# 1-Schematic_Raspberry_Pi2.net
KiCad netlist of a schematic drawn in EasyEDA
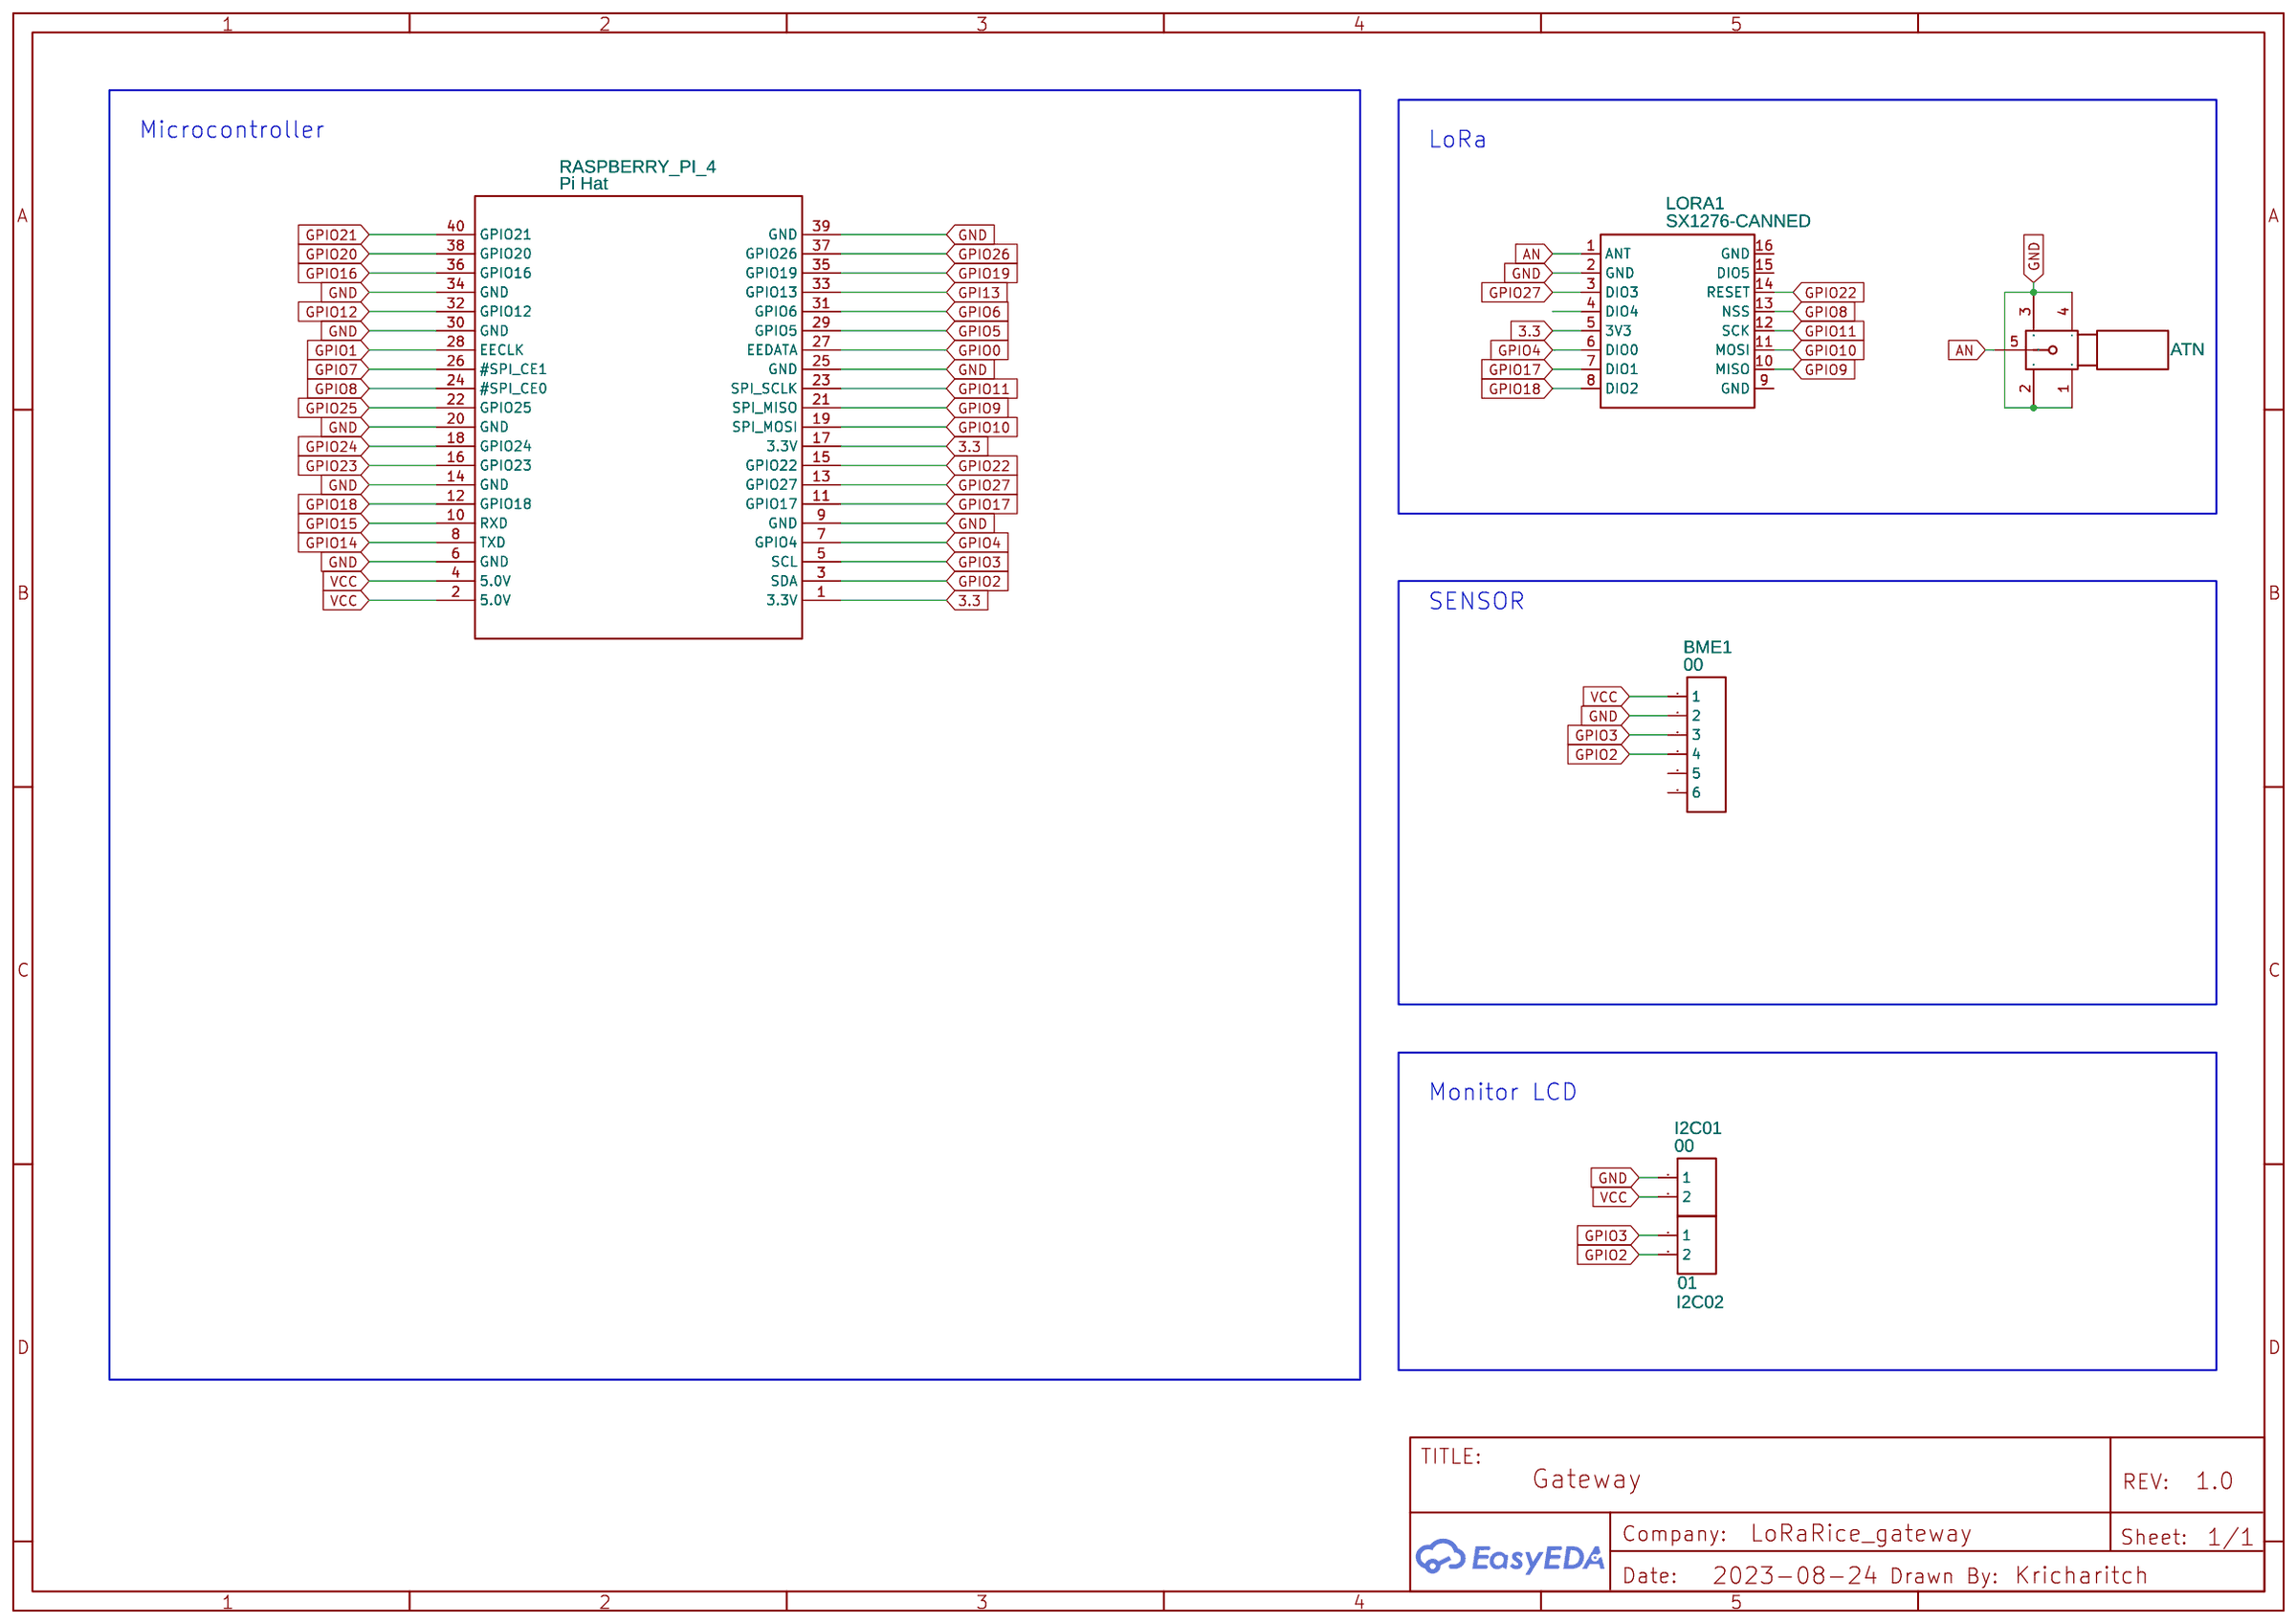
[diagram p0: schematic sheet]

(export (version "E")
  (design (tool "Eeschema 10.0.6"))
  (components
    (comp (ref "BME1") (value "00") (libsource (lib "") (part "HDR-F-2.54_1x6")))
    (comp (ref "I2C01") (value "00") (libsource (lib "") (part "CONN-TH_2P-P5.00")))
    (comp (ref "I2C02") (value "01") (libsource (lib "") (part "CONN-TH_2P-P5.00")))
    (comp (ref "LORA1")
      (value "SX1276-CANNED")
      (fields (field (name "Manufacturer Part") "LoRa1276-C1") (field (name "Manufacturer") "G-NiceRF"))
      (libsource (lib "") (part "SX1276-CANNED"))
    )
    (comp (ref "RASPBERRY_PI_4") (value "Pi Hat") (libsource (lib "") (part "Unknown_280_-75")))
    (comp (ref "RF1")
      (value "ATN")
      (fields
        (field (name "Manufacturer Part") "BWSMA-KE-P001")
        (field (name "Manufacturer") "BAT WIRELESS(蝙蝠无线)")
      )
      (libsource (lib "") (part "BWSMA-KE-P001"))
    )
  )
  (nets
    (net (code "1") (name "3.3") (class "Default")
      (node (ref "LORA1") (pin "5") (pinfunction "3V3_5") (pintype "unspecified"))
      (node (ref "RASPBERRY_PI_4") (pin "1") (pinfunction "3.3V_1") (pintype "unspecified"))
      (node (ref "RASPBERRY_PI_4") (pin "17") (pinfunction "3.3V_17") (pintype "unspecified"))
    )
    (net (code "2") (name "AN") (class "Default")
      (node (ref "LORA1") (pin "1") (pinfunction "ANT_1") (pintype "unspecified"))
      (node (ref "RF1") (pin "5") (pinfunction "5_5") (pintype "unspecified"))
    )
    (net (code "3") (name "GND") (class "Default")
      (node (ref "BME1") (pin "2") (pinfunction "2_2") (pintype "input"))
      (node (ref "I2C01") (pin "1") (pinfunction "1_1") (pintype "unspecified"))
      (node (ref "LORA1") (pin "2") (pinfunction "GND_2") (pintype "unspecified"))
      (node (ref "RASPBERRY_PI_4") (pin "14") (pinfunction "GND_14") (pintype "unspecified"))
      (node (ref "RASPBERRY_PI_4") (pin "20") (pinfunction "GND_20") (pintype "unspecified"))
      (node (ref "RASPBERRY_PI_4") (pin "25") (pinfunction "GND_25") (pintype "unspecified"))
      (node (ref "RASPBERRY_PI_4") (pin "30") (pinfunction "GND_30") (pintype "unspecified"))
      (node (ref "RASPBERRY_PI_4") (pin "34") (pinfunction "GND_34") (pintype "unspecified"))
      (node (ref "RASPBERRY_PI_4") (pin "39") (pinfunction "GND_39") (pintype "unspecified"))
      (node (ref "RASPBERRY_PI_4") (pin "6") (pinfunction "GND_6") (pintype "unspecified"))
      (node (ref "RASPBERRY_PI_4") (pin "9") (pinfunction "GND_9") (pintype "unspecified"))
      (node (ref "RF1") (pin "1") (pinfunction "1_1") (pintype "unspecified"))
      (node (ref "RF1") (pin "2") (pinfunction "2_2") (pintype "unspecified"))
      (node (ref "RF1") (pin "3") (pinfunction "3_3") (pintype "unspecified"))
      (node (ref "RF1") (pin "4") (pinfunction "4_4") (pintype "unspecified"))
    )
    (net (code "4") (name "GPI13") (class "Default")
      (node (ref "RASPBERRY_PI_4") (pin "33") (pinfunction "GPIO13_33") (pintype "unspecified"))
    )
    (net (code "5") (name "GPIO0") (class "Default")
      (node (ref "RASPBERRY_PI_4") (pin "27") (pinfunction "EEDATA_27") (pintype "unspecified"))
    )
    (net (code "6") (name "GPIO1") (class "Default")
      (node (ref "RASPBERRY_PI_4") (pin "28") (pinfunction "EECLK_28") (pintype "unspecified"))
    )
    (net (code "7") (name "GPIO2") (class "Default")
      (node (ref "BME1") (pin "4") (pinfunction "4_4") (pintype "input"))
      (node (ref "I2C02") (pin "2") (pinfunction "2_2") (pintype "unspecified"))
      (node (ref "RASPBERRY_PI_4") (pin "3") (pinfunction "SDA_3") (pintype "unspecified"))
    )
    (net (code "8") (name "GPIO3") (class "Default")
      (node (ref "BME1") (pin "3") (pinfunction "3_3") (pintype "input"))
      (node (ref "I2C02") (pin "1") (pinfunction "1_1") (pintype "unspecified"))
      (node (ref "RASPBERRY_PI_4") (pin "5") (pinfunction "SCL_5") (pintype "unspecified"))
    )
    (net (code "9") (name "GPIO4") (class "Default")
      (node (ref "LORA1") (pin "6") (pinfunction "DIO0_6") (pintype "unspecified"))
      (node (ref "RASPBERRY_PI_4") (pin "7") (pinfunction "GPIO4_7") (pintype "unspecified"))
    )
    (net (code "10") (name "GPIO5") (class "Default")
      (node (ref "RASPBERRY_PI_4") (pin "29") (pinfunction "GPIO5_29") (pintype "unspecified"))
    )
    (net (code "11") (name "GPIO6") (class "Default")
      (node (ref "RASPBERRY_PI_4") (pin "31") (pinfunction "GPIO6_31") (pintype "unspecified"))
    )
    (net (code "12") (name "GPIO7") (class "Default")
      (node (ref "RASPBERRY_PI_4") (pin "26") (pinfunction "#SPI_CE1_26") (pintype "unspecified"))
    )
    (net (code "13") (name "GPIO8") (class "Default")
      (node (ref "LORA1") (pin "13") (pinfunction "NSS_13") (pintype "unspecified"))
      (node (ref "RASPBERRY_PI_4") (pin "24") (pinfunction "#SPI_CE0_24") (pintype "unspecified"))
    )
    (net (code "14") (name "GPIO9") (class "Default")
      (node (ref "LORA1") (pin "10") (pinfunction "MISO_10") (pintype "unspecified"))
      (node (ref "RASPBERRY_PI_4") (pin "21") (pinfunction "SPI_MISO_21") (pintype "unspecified"))
    )
    (net (code "15") (name "GPIO10") (class "Default")
      (node (ref "LORA1") (pin "11") (pinfunction "MOSI_11") (pintype "unspecified"))
      (node (ref "RASPBERRY_PI_4") (pin "19") (pinfunction "SPI_MOSI_19") (pintype "unspecified"))
    )
    (net (code "16") (name "GPIO11") (class "Default")
      (node (ref "LORA1") (pin "12") (pinfunction "SCK_12") (pintype "unspecified"))
      (node (ref "RASPBERRY_PI_4") (pin "23") (pinfunction "SPI_SCLK_23") (pintype "unspecified"))
    )
    (net (code "17") (name "GPIO12") (class "Default")
      (node (ref "RASPBERRY_PI_4") (pin "32") (pinfunction "GPIO12_32") (pintype "unspecified"))
    )
    (net (code "18") (name "GPIO14") (class "Default")
      (node (ref "RASPBERRY_PI_4") (pin "8") (pinfunction "TXD_8") (pintype "output"))
    )
    (net (code "19") (name "GPIO15") (class "Default")
      (node (ref "RASPBERRY_PI_4") (pin "10") (pinfunction "RXD_10") (pintype "unspecified"))
    )
    (net (code "20") (name "GPIO16") (class "Default")
      (node (ref "RASPBERRY_PI_4") (pin "36") (pinfunction "GPIO16_36") (pintype "unspecified"))
    )
    (net (code "21") (name "GPIO17") (class "Default")
      (node (ref "LORA1") (pin "7") (pinfunction "DIO1_7") (pintype "unspecified"))
      (node (ref "RASPBERRY_PI_4") (pin "11") (pinfunction "GPIO17_11") (pintype "unspecified"))
    )
    (net (code "22") (name "GPIO18") (class "Default")
      (node (ref "LORA1") (pin "8") (pinfunction "DIO2_8") (pintype "unspecified"))
      (node (ref "RASPBERRY_PI_4") (pin "12") (pinfunction "GPIO18_12") (pintype "unspecified"))
    )
    (net (code "23") (name "GPIO19") (class "Default")
      (node (ref "RASPBERRY_PI_4") (pin "35") (pinfunction "GPIO19_35") (pintype "unspecified"))
    )
    (net (code "24") (name "GPIO20") (class "Default")
      (node (ref "RASPBERRY_PI_4") (pin "38") (pinfunction "GPIO20_38") (pintype "unspecified"))
    )
    (net (code "25") (name "GPIO21") (class "Default")
      (node (ref "RASPBERRY_PI_4") (pin "40") (pinfunction "GPIO21_40") (pintype "unspecified"))
    )
    (net (code "26") (name "GPIO22") (class "Default")
      (node (ref "LORA1") (pin "14") (pinfunction "RESET_14") (pintype "unspecified"))
      (node (ref "RASPBERRY_PI_4") (pin "15") (pinfunction "GPIO22_15") (pintype "unspecified"))
    )
    (net (code "27") (name "GPIO23") (class "Default")
      (node (ref "RASPBERRY_PI_4") (pin "16") (pinfunction "GPIO23_16") (pintype "unspecified"))
    )
    (net (code "28") (name "GPIO24") (class "Default")
      (node (ref "RASPBERRY_PI_4") (pin "18") (pinfunction "GPIO24_18") (pintype "unspecified"))
    )
    (net (code "29") (name "GPIO25") (class "Default")
      (node (ref "RASPBERRY_PI_4") (pin "22") (pinfunction "GPIO25_22") (pintype "unspecified"))
    )
    (net (code "30") (name "GPIO26") (class "Default")
      (node (ref "RASPBERRY_PI_4") (pin "37") (pinfunction "GPIO26_37") (pintype "unspecified"))
    )
    (net (code "31") (name "GPIO27") (class "Default")
      (node (ref "LORA1") (pin "3") (pinfunction "DIO3_3") (pintype "unspecified"))
      (node (ref "RASPBERRY_PI_4") (pin "13") (pinfunction "GPIO27_13") (pintype "unspecified"))
    )
    (net (code "32") (name "VCC") (class "Default")
      (node (ref "BME1") (pin "1") (pinfunction "1_1") (pintype "input"))
      (node (ref "I2C01") (pin "2") (pinfunction "2_2") (pintype "unspecified"))
      (node (ref "RASPBERRY_PI_4") (pin "2") (pinfunction "5.0V_2") (pintype "unspecified"))
      (node (ref "RASPBERRY_PI_4") (pin "4") (pinfunction "5.0V_4") (pintype "unspecified"))
    )
    (net (code "33") (name "unconnected-(BME1-Pad5)") (class "Default")
      (node (ref "BME1") (pin "5") (pinfunction "5_5") (pintype "input"))
    )
    (net (code "34") (name "unconnected-(BME1-Pad6)") (class "Default")
      (node (ref "BME1") (pin "6") (pinfunction "6_6") (pintype "input"))
    )
    (net (code "35") (name "unconnected-(LORA1-DIO4-Pad4)") (class "Default")
      (node (ref "LORA1") (pin "4") (pinfunction "DIO4_4") (pintype "unspecified"))
    )
    (net (code "36") (name "unconnected-(LORA1-DIO5-Pad15)") (class "Default")
      (node (ref "LORA1") (pin "15") (pinfunction "DIO5_15") (pintype "unspecified"))
    )
    (net (code "37") (name "unconnected-(LORA1-GND-Pad9)") (class "Default")
      (node (ref "LORA1") (pin "9") (pinfunction "GND_9") (pintype "unspecified"))
    )
    (net (code "38") (name "unconnected-(LORA1-GND-Pad16)") (class "Default")
      (node (ref "LORA1") (pin "16") (pinfunction "GND_16") (pintype "unspecified"))
    )
  )
)
